# SNES_RGBAmp_wCSYNC.net
KiCad netlist of a schematic drawn in EAGLE
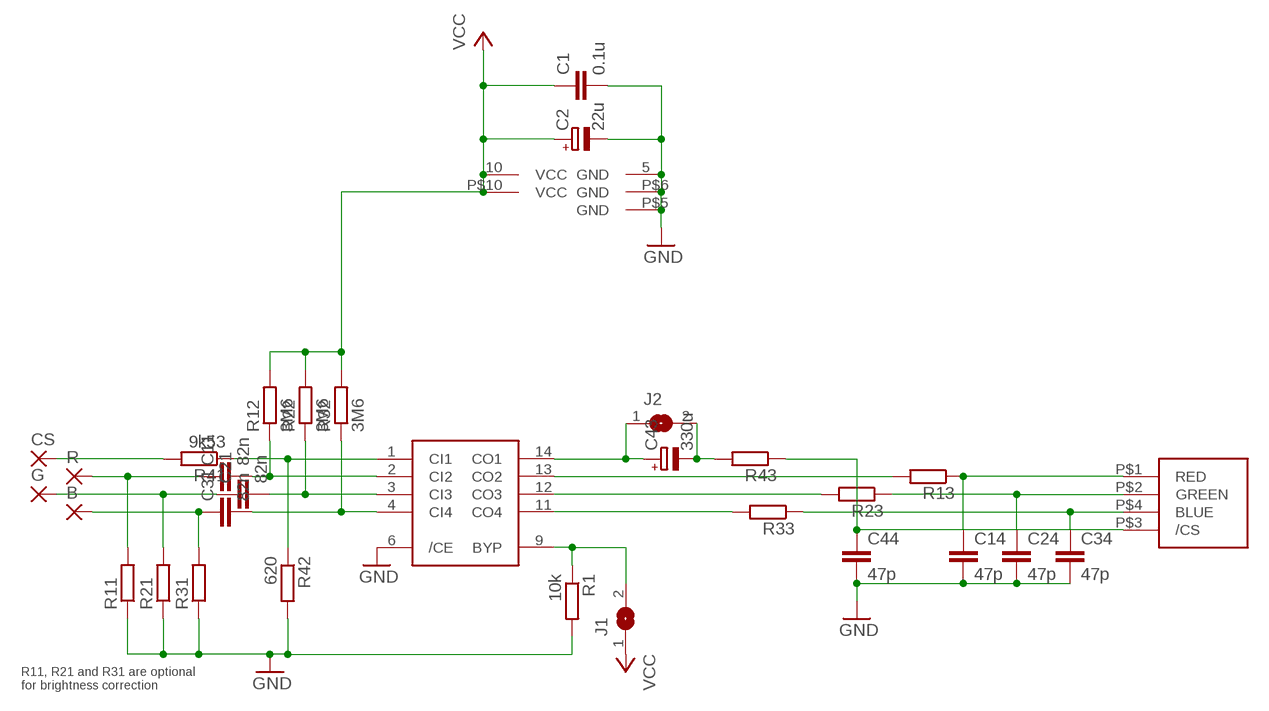
[diagram p0: schematic, sheet 1]

(export (version "E")
  (design (tool "Eeschema 10.0.6"))
  (components
    (comp (ref "B")
      (value "SMD2")
      (footprint "eagle-import:SMD1,27-2,54")
      (libsource (lib "eagle-import") (part "SMD2"))
    )
    (comp (ref "C1")
      (value "0.1u")
      (footprint "eagle-import:C0603K")
      (libsource (lib "eagle-import") (part "C-EUC0603K"))
    )
    (comp (ref "C2")
      (value "22u")
      (footprint "eagle-import:SMC_B")
      (libsource (lib "eagle-import") (part "CPOL-EUSMCB"))
    )
    (comp (ref "C11")
      (value "82n")
      (footprint "eagle-import:C0603K")
      (libsource (lib "eagle-import") (part "C-EUC0603K"))
    )
    (comp (ref "C14")
      (value "47p")
      (footprint "eagle-import:C0603K")
      (libsource (lib "eagle-import") (part "C-EUC0603K"))
    )
    (comp (ref "C21")
      (value "82n")
      (footprint "eagle-import:C0603K")
      (libsource (lib "eagle-import") (part "C-EUC0603K"))
    )
    (comp (ref "C24")
      (value "47p")
      (footprint "eagle-import:C0603K")
      (libsource (lib "eagle-import") (part "C-EUC0603K"))
    )
    (comp (ref "C31")
      (value "82n")
      (footprint "eagle-import:C0603K")
      (libsource (lib "eagle-import") (part "C-EUC0603K"))
    )
    (comp (ref "C34")
      (value "47p")
      (footprint "eagle-import:C0603K")
      (libsource (lib "eagle-import") (part "C-EUC0603K"))
    )
    (comp (ref "C43")
      (value "330u")
      (footprint "eagle-import:SMC_D")
      (libsource (lib "eagle-import") (part "CPOL-EUSMCD"))
    )
    (comp (ref "C44")
      (value "47p")
      (footprint "eagle-import:C0603K")
      (libsource (lib "eagle-import") (part "C-EUC0603K"))
    )
    (comp (ref "CS")
      (value "SMD2")
      (footprint "eagle-import:SMD1,27-2,54")
      (libsource (lib "eagle-import") (part "SMD2"))
    )
    (comp (ref "G")
      (value "SMD2")
      (footprint "eagle-import:SMD1,27-2,54")
      (libsource (lib "eagle-import") (part "SMD2"))
    )
    (comp (ref "J1") (value "SJ") (footprint "eagle-import:SJ") (libsource (lib "eagle-import") (part "SJ")))
    (comp (ref "J2") (value "SJ") (footprint "eagle-import:SJ") (libsource (lib "eagle-import") (part "SJ")))
    (comp (ref "J3")
      (value "SNES_MULTIAV_RGBC_ONLY")
      (footprint "eagle-import:SNES_MULTIAV_RGBC_ONLY")
      (libsource (lib "eagle-import") (part "SNES_MULTIAV_RGBC_ONLY"))
    )
    (comp (ref "R")
      (value "SMD2")
      (footprint "eagle-import:SMD1,27-2,54")
      (libsource (lib "eagle-import") (part "SMD2"))
    )
    (comp (ref "R1")
      (value "10k")
      (footprint "eagle-import:R0603")
      (libsource (lib "eagle-import") (part "R-EU_R0603"))
    )
    (comp (ref "R11")
      (value "R-EU_R0603")
      (footprint "eagle-import:R0603")
      (libsource (lib "eagle-import") (part "R-EU_R0603"))
    )
    (comp (ref "R12")
      (value "3M6")
      (footprint "eagle-import:R0603")
      (libsource (lib "eagle-import") (part "R-EU_R0603"))
    )
    (comp (ref "R13")
      (value "R-EU_R0603")
      (footprint "eagle-import:R0603")
      (libsource (lib "eagle-import") (part "R-EU_R0603"))
    )
    (comp (ref "R21")
      (value "R-EU_R0603")
      (footprint "eagle-import:R0603")
      (libsource (lib "eagle-import") (part "R-EU_R0603"))
    )
    (comp (ref "R22")
      (value "3M6")
      (footprint "eagle-import:R0603")
      (libsource (lib "eagle-import") (part "R-EU_R0603"))
    )
    (comp (ref "R23")
      (value "R-EU_R0603")
      (footprint "eagle-import:R0603")
      (libsource (lib "eagle-import") (part "R-EU_R0603"))
    )
    (comp (ref "R31")
      (value "R-EU_R0603")
      (footprint "eagle-import:R0603")
      (libsource (lib "eagle-import") (part "R-EU_R0603"))
    )
    (comp (ref "R32")
      (value "3M6")
      (footprint "eagle-import:R0603")
      (libsource (lib "eagle-import") (part "R-EU_R0603"))
    )
    (comp (ref "R33")
      (value "R-EU_R0603")
      (footprint "eagle-import:R0603")
      (libsource (lib "eagle-import") (part "R-EU_R0603"))
    )
    (comp (ref "R41")
      (value "9k53")
      (footprint "eagle-import:R0603")
      (libsource (lib "eagle-import") (part "R-EU_R0603"))
    )
    (comp (ref "R42")
      (value "620")
      (footprint "eagle-import:R0603")
      (libsource (lib "eagle-import") (part "R-EU_R0603"))
    )
    (comp (ref "R43")
      (value "R-EU_R0603")
      (footprint "eagle-import:R0603")
      (libsource (lib "eagle-import") (part "R-EU_R0603"))
    )
    (comp (ref "U1")
      (value "THS7374")
      (footprint "eagle-import:THS7374")
      (libsource (lib "eagle-import") (part "THS7374"))
    )
  )
  (nets
    (net (code "1") (name "GND") (class "Default")
      (node (ref "C1") (pin "2") (pinfunction "2_2") (pintype "passive"))
      (node (ref "C14") (pin "2") (pinfunction "2_2") (pintype "passive"))
      (node (ref "C2") (pin "-") (pinfunction "-_-") (pintype "passive"))
      (node (ref "C24") (pin "2") (pinfunction "2_2") (pintype "passive"))
      (node (ref "C34") (pin "2") (pinfunction "2_2") (pintype "passive"))
      (node (ref "C44") (pin "2") (pinfunction "2_2") (pintype "passive"))
      (node (ref "J3") (pin "P$5") (pinfunction "GND_P$5") (pintype "bidirectional"))
      (node (ref "J3") (pin "P$6") (pinfunction "GND_P$6") (pintype "bidirectional"))
      (node (ref "R1") (pin "2") (pinfunction "2_2") (pintype "passive"))
      (node (ref "R11") (pin "1") (pinfunction "1_1") (pintype "passive"))
      (node (ref "R21") (pin "1") (pinfunction "1_1") (pintype "passive"))
      (node (ref "R31") (pin "1") (pinfunction "1_1") (pintype "passive"))
      (node (ref "R42") (pin "2") (pinfunction "2_2") (pintype "passive"))
      (node (ref "U1") (pin "5") (pinfunction "GND_5") (pintype "bidirectional"))
      (node (ref "U1") (pin "6") (pinfunction "/CE_6") (pintype "bidirectional"))
    )
    (net (code "2") (name "Net-(B-P)") (class "Default")
      (node (ref "B") (pin "1") (pinfunction "P_1") (pintype "passive"))
      (node (ref "C31") (pin "1") (pinfunction "1_1") (pintype "passive"))
      (node (ref "R31") (pin "2") (pinfunction "2_2") (pintype "passive"))
    )
    (net (code "3") (name "Net-(C43-Pad-)") (class "Default")
      (node (ref "C43") (pin "-") (pinfunction "-_-") (pintype "passive"))
      (node (ref "J2") (pin "2") (pinfunction "2_2") (pintype "passive"))
      (node (ref "R43") (pin "2") (pinfunction "2_2") (pintype "passive"))
    )
    (net (code "4") (name "Net-(CS-P)") (class "Default")
      (node (ref "CS") (pin "1") (pinfunction "P_1") (pintype "passive"))
      (node (ref "R41") (pin "2") (pinfunction "2_2") (pintype "passive"))
    )
    (net (code "5") (name "Net-(G-P)") (class "Default")
      (node (ref "C21") (pin "1") (pinfunction "1_1") (pintype "passive"))
      (node (ref "G") (pin "1") (pinfunction "P_1") (pintype "passive"))
      (node (ref "R21") (pin "2") (pinfunction "2_2") (pintype "passive"))
    )
    (net (code "6") (name "Net-(J3A-BLUE)") (class "Default")
      (node (ref "C34") (pin "1") (pinfunction "1_1") (pintype "passive"))
      (node (ref "J3") (pin "P$4") (pinfunction "BLUE_P$4") (pintype "bidirectional"))
      (node (ref "R33") (pin "1") (pinfunction "1_1") (pintype "passive"))
    )
    (net (code "7") (name "Net-(J3A-GREEN)") (class "Default")
      (node (ref "C24") (pin "1") (pinfunction "1_1") (pintype "passive"))
      (node (ref "J3") (pin "P$2") (pinfunction "GREEN_P$2") (pintype "bidirectional"))
      (node (ref "R23") (pin "1") (pinfunction "1_1") (pintype "passive"))
    )
    (net (code "8") (name "Net-(J3A-RED)") (class "Default")
      (node (ref "C14") (pin "1") (pinfunction "1_1") (pintype "passive"))
      (node (ref "J3") (pin "P$1") (pinfunction "RED_P$1") (pintype "bidirectional"))
      (node (ref "R13") (pin "1") (pinfunction "1_1") (pintype "passive"))
    )
    (net (code "9") (name "Net-(J3A-{slash}CS)") (class "Default")
      (node (ref "C44") (pin "1") (pinfunction "1_1") (pintype "passive"))
      (node (ref "J3") (pin "P$3") (pinfunction "/CS_P$3") (pintype "bidirectional"))
      (node (ref "R43") (pin "1") (pinfunction "1_1") (pintype "passive"))
    )
    (net (code "10") (name "Net-(R-P)") (class "Default")
      (node (ref "C11") (pin "1") (pinfunction "1_1") (pintype "passive"))
      (node (ref "R") (pin "1") (pinfunction "P_1") (pintype "passive"))
      (node (ref "R11") (pin "2") (pinfunction "2_2") (pintype "passive"))
    )
    (net (code "11") (name "Net-(U1A-BYP)") (class "Default")
      (node (ref "J1") (pin "2") (pinfunction "2_2") (pintype "passive"))
      (node (ref "R1") (pin "1") (pinfunction "1_1") (pintype "passive"))
      (node (ref "U1") (pin "9") (pinfunction "BYP_9") (pintype "bidirectional"))
    )
    (net (code "12") (name "Net-(U1A-CI1)") (class "Default")
      (node (ref "R41") (pin "1") (pinfunction "1_1") (pintype "passive"))
      (node (ref "R42") (pin "1") (pinfunction "1_1") (pintype "passive"))
      (node (ref "U1") (pin "1") (pinfunction "CI1_1") (pintype "bidirectional"))
    )
    (net (code "13") (name "Net-(U1A-CI2)") (class "Default")
      (node (ref "C11") (pin "2") (pinfunction "2_2") (pintype "passive"))
      (node (ref "R12") (pin "1") (pinfunction "1_1") (pintype "passive"))
      (node (ref "U1") (pin "2") (pinfunction "CI2_2") (pintype "bidirectional"))
    )
    (net (code "14") (name "Net-(U1A-CI3)") (class "Default")
      (node (ref "C21") (pin "2") (pinfunction "2_2") (pintype "passive"))
      (node (ref "R22") (pin "1") (pinfunction "1_1") (pintype "passive"))
      (node (ref "U1") (pin "3") (pinfunction "CI3_3") (pintype "bidirectional"))
    )
    (net (code "15") (name "Net-(U1A-CI4)") (class "Default")
      (node (ref "C31") (pin "2") (pinfunction "2_2") (pintype "passive"))
      (node (ref "R32") (pin "1") (pinfunction "1_1") (pintype "passive"))
      (node (ref "U1") (pin "4") (pinfunction "CI4_4") (pintype "bidirectional"))
    )
    (net (code "16") (name "Net-(U1A-CO1)") (class "Default")
      (node (ref "C43") (pin "+") (pinfunction "+_+") (pintype "passive"))
      (node (ref "J2") (pin "1") (pinfunction "1_1") (pintype "passive"))
      (node (ref "U1") (pin "14") (pinfunction "CO1_14") (pintype "bidirectional"))
    )
    (net (code "17") (name "Net-(U1A-CO2)") (class "Default")
      (node (ref "R13") (pin "2") (pinfunction "2_2") (pintype "passive"))
      (node (ref "U1") (pin "13") (pinfunction "CO2_13") (pintype "bidirectional"))
    )
    (net (code "18") (name "Net-(U1A-CO3)") (class "Default")
      (node (ref "R23") (pin "2") (pinfunction "2_2") (pintype "passive"))
      (node (ref "U1") (pin "12") (pinfunction "CO3_12") (pintype "bidirectional"))
    )
    (net (code "19") (name "Net-(U1A-CO4)") (class "Default")
      (node (ref "R33") (pin "2") (pinfunction "2_2") (pintype "passive"))
      (node (ref "U1") (pin "11") (pinfunction "CO4_11") (pintype "bidirectional"))
    )
    (net (code "20") (name "VCC") (class "Default")
      (node (ref "C1") (pin "1") (pinfunction "1_1") (pintype "passive"))
      (node (ref "C2") (pin "+") (pinfunction "+_+") (pintype "passive"))
      (node (ref "J1") (pin "1") (pinfunction "1_1") (pintype "passive"))
      (node (ref "J3") (pin "P$10") (pinfunction "VCC_P$10") (pintype "bidirectional"))
      (node (ref "R12") (pin "2") (pinfunction "2_2") (pintype "passive"))
      (node (ref "R22") (pin "2") (pinfunction "2_2") (pintype "passive"))
      (node (ref "R32") (pin "2") (pinfunction "2_2") (pintype "passive"))
      (node (ref "U1") (pin "10") (pinfunction "VCC_10") (pintype "bidirectional"))
    )
  )
)
